# driver2.net
KiCad netlist of a schematic drawn in Altium Designer
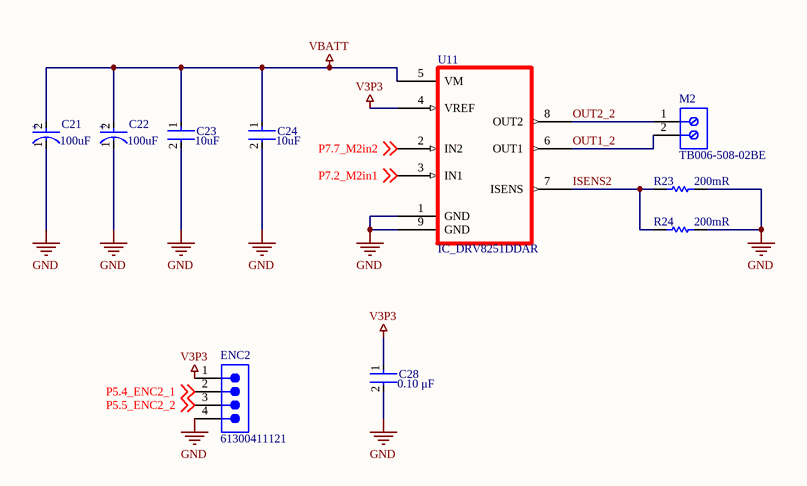
[diagram p0: driver2.SchDoc]

(export (version "E")
  (design (tool "Eeschema 10.0.6"))
  (components
    (comp (ref "C21")
      (value "100uF")
      (footprint "FP-SD8-MFG")
      (description "CAP ALUM 100UF 20% 25V SMD")
      (fields (field (name "VOLTAGE") "25V") (field (name "TOLERANCE") "20%"))
      (libsource (lib "Altium Content Vault") (part "a00bbbee19879c290e62620ae7e47b1"))
    )
    (comp (ref "C22")
      (value "100uF")
      (footprint "FP-SD8-MFG")
      (description "CAP ALUM 100UF 20% 25V SMD")
      (fields (field (name "VOLTAGE") "25V") (field (name "TOLERANCE") "20%"))
      (libsource (lib "Altium Content Vault") (part "a00bbbee19879c290e62620ae7e47b1"))
    )
    (comp (ref "C23")
      (value "10uF")
      (footprint "FP-C0805C-DG-MFG")
      (description "CAP CER 10UF 10V X5R 0805")
      (fields
        (field (name "MANUFACTURER") "KEMET")
        (field (name "MANUFACTURER PART NUMBER") "C0805C106K8PACTU")
      )
      (libsource (lib "Altium Content Vault") (part "11868f565c42a9108669ba33697ecf6"))
    )
    (comp (ref "C24")
      (value "10uF")
      (footprint "FP-C0805C-DG-MFG")
      (description "CAP CER 10UF 10V X5R 0805")
      (fields
        (field (name "MANUFACTURER") "KEMET")
        (field (name "MANUFACTURER PART NUMBER") "C0805C106K8PACTU")
      )
      (libsource (lib "Altium Content Vault") (part "11868f565c42a9108669ba33697ecf6"))
    )
    (comp (ref "C28")
      (value "C0805C104K5RACTU")
      (footprint "FP-C0805C-DN-MFG")
      (description "CAP CER 0.1UF 50V X7R 0805")
      (fields
        (field (name "MANUFACTURER") "KEMET")
        (field (name "OCTOPART") "https://octopart.com/c0805c104k5ractu-kemet-143926")
        (field (name "CAPACITANCE") "0.10 μF")
      )
      (libsource (lib "Altium Content Vault") (part "b4654b650e69147ec39a6b967a45e02"))
    )
    (comp (ref "ENC2")
      (value "61300411121")
      (footprint "61300411121")
      (libsource (lib "Altium Content Vault") (part "Header_Male_1R_04P"))
    )
    (comp (ref "M2")
      (value "CONN_TB006_-508-02BE")
      (footprint "CUI_TB006 -508-02BE")
      (description "2~24 Poles, Screw Type, Horizontal, 5.08 Pitch, 26~14 (AWG), Terminal Block Connector")
      (fields
        (field (name "MF") "CUI Devices")
        (field (name "MP") "TB006 -508-02BE")
        (field (name "MANUFACTURER PART NUMBER") "TB006-508-02BE")
      )
      (libsource (lib "ECE453_S24") (part "CONN_TB006_-508-02BE"))
    )
    (comp (ref "R23")
      (value "200mR")
      (footprint "RESC2013X60X40LL20T25")
      (description "RES 0.2 OHM 1% 1/2W 0805")
      (fields
        (field (name "MANUFACTURER") "Panasonic")
        (field (name "MANUFACTURER PART NUMBER") "ERJ-6DSFR20V")
      )
      (libsource (lib "Altium Content Vault") (part "RES"))
    )
    (comp (ref "R24")
      (value "200mR")
      (footprint "RESC2013X60X40LL20T25")
      (description "RES 0.2 OHM 1% 1/2W 0805")
      (fields
        (field (name "MANUFACTURER") "Panasonic")
        (field (name "MANUFACTURER PART NUMBER") "ERJ-6DSFR20V")
      )
      (libsource (lib "Altium Content Vault") (part "RES"))
    )
    (comp (ref "U11")
      (value "IC_DRV8251DDAR")
      (footprint "SOIC_8_PP")
      (description "48-V, 3.5-A H bridge motor driver with current regulation and latched OCP 8-SO PowerPAD -40 to 150")
      (libsource (lib "uw-madison-parts") (part "IC_DRV8251DDAR"))
    )
  )
  (nets
    (net (code "1") (name "/ISENS2") (class "Default")
      (node (ref "R23") (pin "2") (pinfunction "2_2") (pintype "passive"))
      (node (ref "R24") (pin "2") (pinfunction "2_2") (pintype "passive"))
      (node (ref "U11") (pin "7") (pinfunction "ISENS_7") (pintype "output"))
    )
    (net (code "2") (name "/OUT1_2") (class "Default")
      (node (ref "M2") (pin "2") (pinfunction "2_2") (pintype "passive"))
      (node (ref "U11") (pin "6") (pinfunction "OUT1_6") (pintype "output"))
    )
    (net (code "3") (name "/OUT2_2") (class "Default")
      (node (ref "M2") (pin "1") (pinfunction "1_1") (pintype "passive"))
      (node (ref "U11") (pin "8") (pinfunction "OUT2_8") (pintype "output"))
    )
    (net (code "4") (name "GND") (class "Default")
      (node (ref "C21") (pin "1") (pinfunction "C_1") (pintype "passive"))
      (node (ref "C22") (pin "1") (pinfunction "C_1") (pintype "passive"))
      (node (ref "C23") (pin "2") (pinfunction "2_2") (pintype "passive"))
      (node (ref "C24") (pin "2") (pinfunction "2_2") (pintype "passive"))
      (node (ref "C28") (pin "2") (pinfunction "2_2") (pintype "passive"))
      (node (ref "ENC2") (pin "4") (pinfunction "4_4") (pintype "passive"))
      (node (ref "R23") (pin "1") (pinfunction "1_1") (pintype "passive"))
      (node (ref "R24") (pin "1") (pinfunction "1_1") (pintype "passive"))
      (node (ref "U11") (pin "1") (pinfunction "GND_1") (pintype "power_in"))
      (node (ref "U11") (pin "9") (pinfunction "GND_9") (pintype "power_in"))
    )
    (net (code "5") (name "P5.4_ENC2_1") (class "Default")
      (node (ref "ENC2") (pin "2") (pinfunction "2_2") (pintype "passive"))
    )
    (net (code "6") (name "P5.5_ENC2_2") (class "Default")
      (node (ref "ENC2") (pin "3") (pinfunction "3_3") (pintype "passive"))
    )
    (net (code "7") (name "P7.2_M2in1") (class "Default")
      (node (ref "U11") (pin "3") (pinfunction "IN1_3") (pintype "input"))
    )
    (net (code "8") (name "P7.7_M2in2") (class "Default")
      (node (ref "U11") (pin "2") (pinfunction "IN2_2") (pintype "input"))
    )
    (net (code "9") (name "V3P3") (class "Default")
      (node (ref "C28") (pin "1") (pinfunction "1_1") (pintype "passive"))
      (node (ref "ENC2") (pin "1") (pinfunction "1_1") (pintype "passive"))
      (node (ref "U11") (pin "4") (pinfunction "VREF_4") (pintype "input"))
    )
    (net (code "10") (name "VBATT") (class "Default")
      (node (ref "C21") (pin "2") (pinfunction "A_2") (pintype "passive"))
      (node (ref "C22") (pin "2") (pinfunction "A_2") (pintype "passive"))
      (node (ref "C23") (pin "1") (pinfunction "1_1") (pintype "passive"))
      (node (ref "C24") (pin "1") (pinfunction "1_1") (pintype "passive"))
      (node (ref "U11") (pin "5") (pinfunction "VM_5") (pintype "power_in"))
    )
  )
)
